# 04_PCIe_VL805.net
KiCad netlist of a schematic drawn in Altium Designer
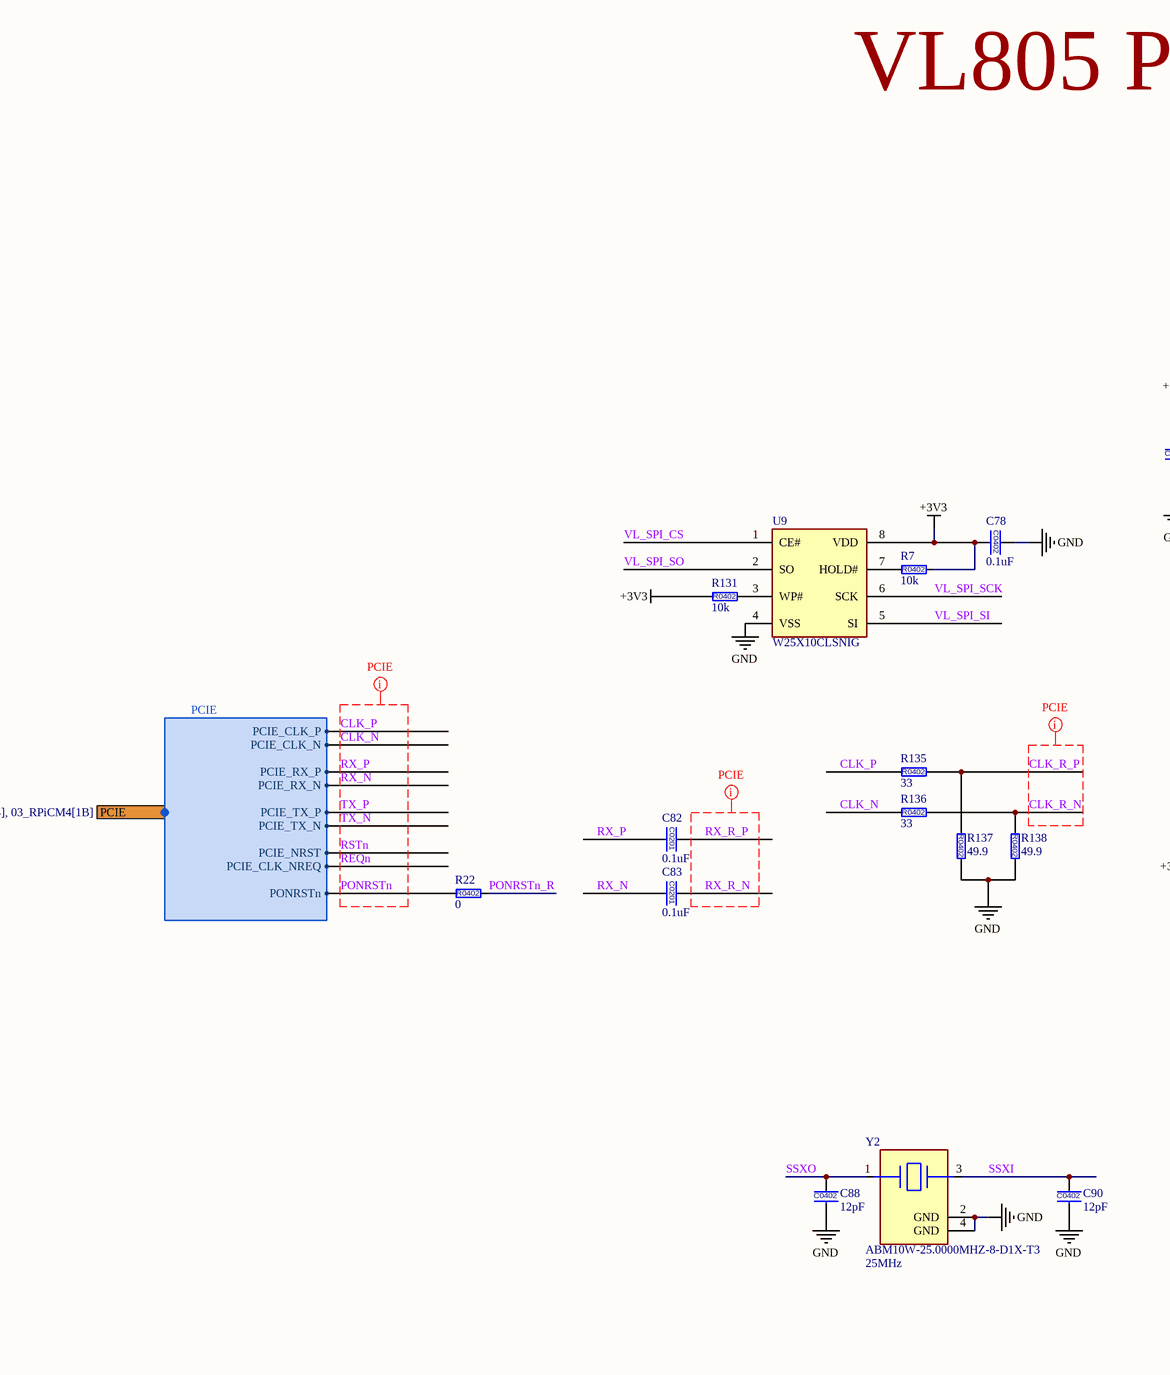
[diagram p0: 04_PCIe_VL805.SchDoc, left]
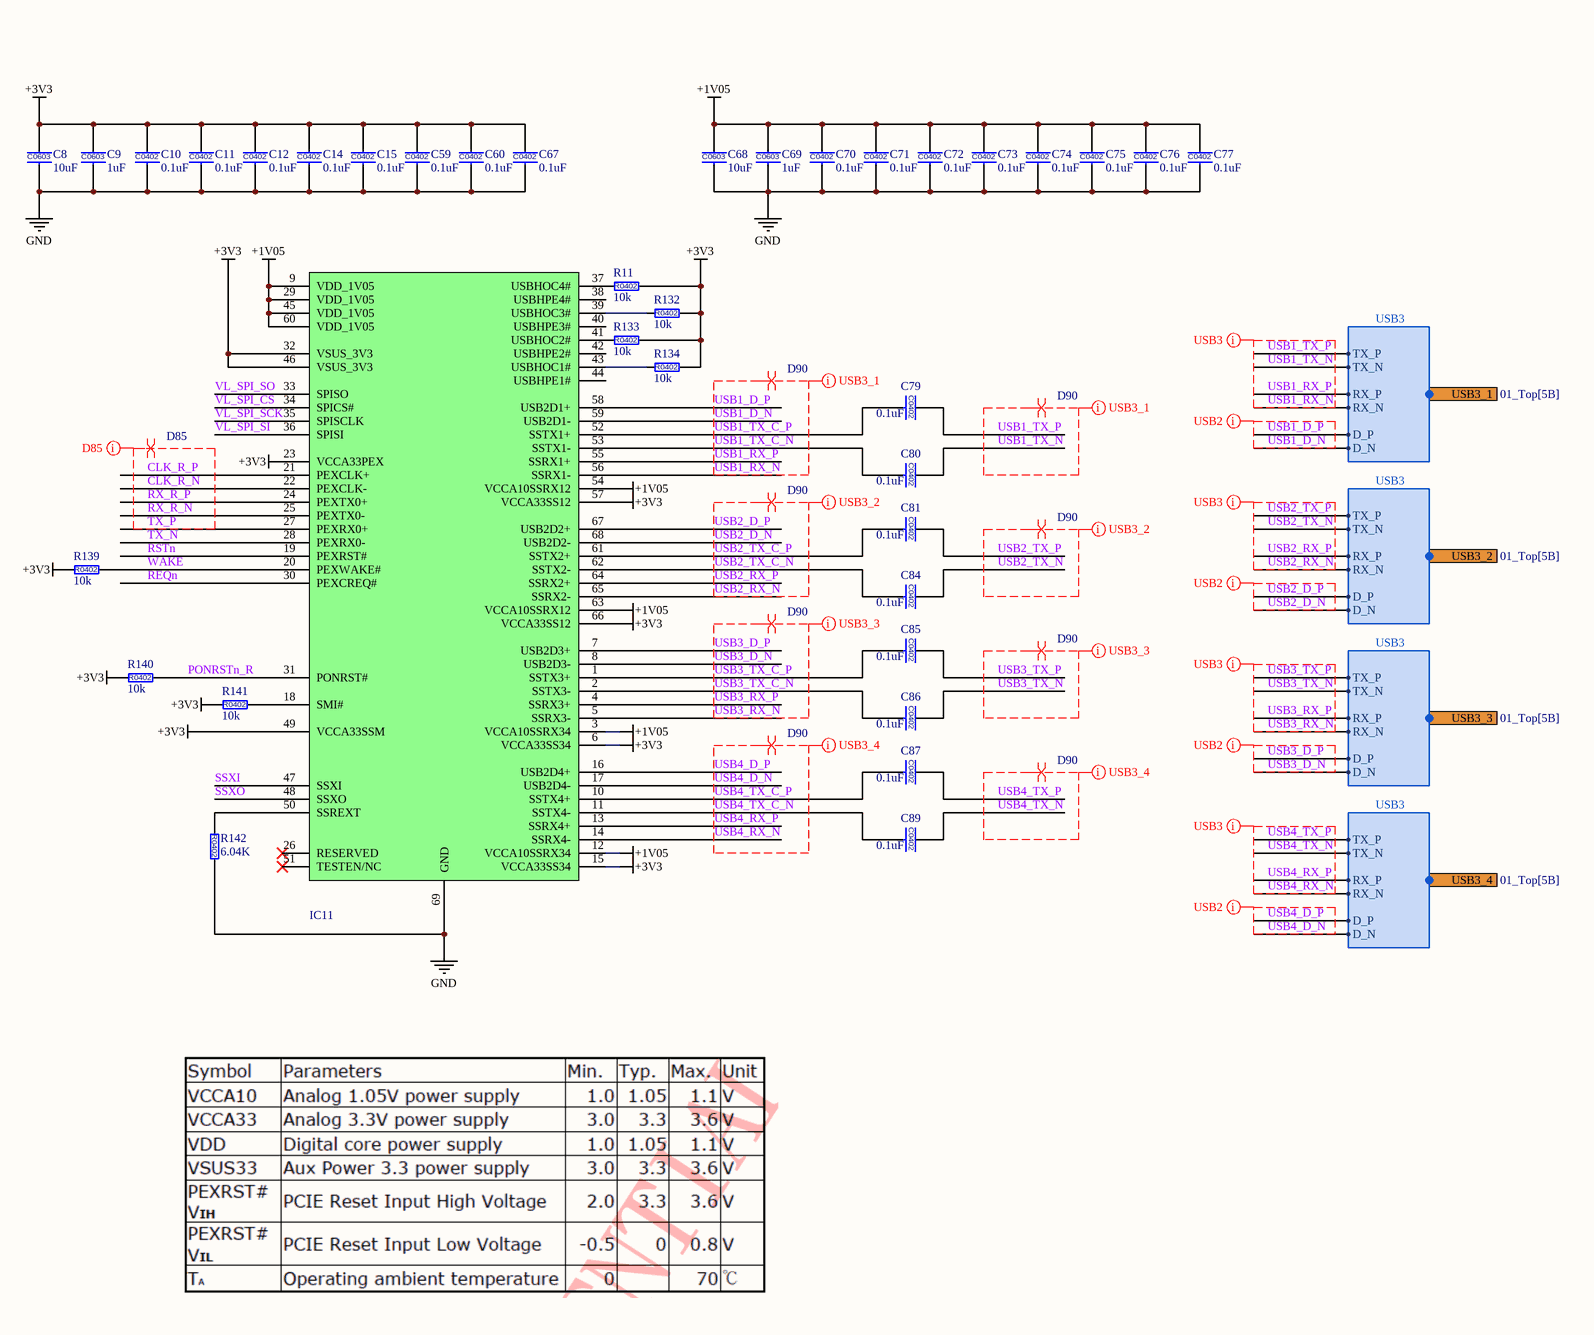
[diagram p1: 04_PCIe_VL805.SchDoc, right]

(export (version "E")
  (design (tool "Eeschema 10.0.6"))
  (components
    (comp (ref "C8")
      (value "10uF")
      (footprint "C0603")
      (description "CAP CER 10uF 10% 10V X5R 0603")
      (fields
        (field (name "MANUFACTURER") "KYOCERA AVX")
        (field (name "MANUFACTURER PART NUMBER") "0603ZD106KAT2A")
      )
      (libsource (lib "Capacitor") (part "0603ZD106KAT2A"))
    )
    (comp (ref "C9")
      (value "1uF")
      (footprint "C0603")
      (description "CAP CER 1uF 20% 10V X5R 0603")
      (fields (field (name "TOLERANCE") "20%") (field (name "MANUFACTURER") "KYOCERA AVX"))
      (libsource (lib "Capacitor") (part "0201ZD105MAT2A"))
    )
    (comp (ref "C10")
      (value "0.1uF")
      (footprint "C0402")
      (description "CAP CER  0.1uF 10% 25V X5R 0402")
      (fields
        (field (name "MANUFACTURER") "AVX Corporation")
        (field (name "MANUFACTURER PART NUMBER") "04023D104KAT2A")
      )
      (libsource (lib "Capacitor") (part "04023D104KAT2A"))
    )
    (comp (ref "C11")
      (value "0.1uF")
      (footprint "C0402")
      (description "CAP CER  0.1uF 10% 25V X5R 0402")
      (fields
        (field (name "MANUFACTURER") "AVX Corporation")
        (field (name "MANUFACTURER PART NUMBER") "04023D104KAT2A")
      )
      (libsource (lib "Capacitor") (part "04023D104KAT2A"))
    )
    (comp (ref "C12")
      (value "0.1uF")
      (footprint "C0402")
      (description "CAP CER  0.1uF 10% 25V X5R 0402")
      (fields
        (field (name "MANUFACTURER") "AVX Corporation")
        (field (name "MANUFACTURER PART NUMBER") "04023D104KAT2A")
      )
      (libsource (lib "Capacitor") (part "04023D104KAT2A"))
    )
    (comp (ref "C14")
      (value "0.1uF")
      (footprint "C0402")
      (description "CAP CER  0.1uF 10% 25V X5R 0402")
      (fields
        (field (name "MANUFACTURER") "AVX Corporation")
        (field (name "MANUFACTURER PART NUMBER") "04023D104KAT2A")
      )
      (libsource (lib "Capacitor") (part "04023D104KAT2A"))
    )
    (comp (ref "C15")
      (value "0.1uF")
      (footprint "C0402")
      (description "CAP CER  0.1uF 10% 25V X5R 0402")
      (fields
        (field (name "MANUFACTURER") "AVX Corporation")
        (field (name "MANUFACTURER PART NUMBER") "04023D104KAT2A")
      )
      (libsource (lib "Capacitor") (part "04023D104KAT2A"))
    )
    (comp (ref "C59")
      (value "0.1uF")
      (footprint "C0402")
      (description "CAP CER  0.1uF 10% 25V X5R 0402")
      (fields
        (field (name "MANUFACTURER") "AVX Corporation")
        (field (name "MANUFACTURER PART NUMBER") "04023D104KAT2A")
      )
      (libsource (lib "Capacitor") (part "04023D104KAT2A"))
    )
    (comp (ref "C60")
      (value "0.1uF")
      (footprint "C0402")
      (description "CAP CER  0.1uF 10% 25V X5R 0402")
      (fields
        (field (name "MANUFACTURER") "AVX Corporation")
        (field (name "MANUFACTURER PART NUMBER") "04023D104KAT2A")
      )
      (libsource (lib "Capacitor") (part "04023D104KAT2A"))
    )
    (comp (ref "C67")
      (value "0.1uF")
      (footprint "C0402")
      (description "CAP CER  0.1uF 10% 25V X5R 0402")
      (fields
        (field (name "MANUFACTURER") "AVX Corporation")
        (field (name "MANUFACTURER PART NUMBER") "04023D104KAT2A")
      )
      (libsource (lib "Capacitor") (part "04023D104KAT2A"))
    )
    (comp (ref "C68")
      (value "10uF")
      (footprint "C0603")
      (description "CAP CER 10uF 10% 10V X5R 0603")
      (fields
        (field (name "MANUFACTURER") "KYOCERA AVX")
        (field (name "MANUFACTURER PART NUMBER") "0603ZD106KAT2A")
      )
      (libsource (lib "Capacitor") (part "0603ZD106KAT2A"))
    )
    (comp (ref "C69")
      (value "1uF")
      (footprint "C0603")
      (description "CAP CER 1uF 20% 10V X5R 0603")
      (fields (field (name "TOLERANCE") "20%") (field (name "MANUFACTURER") "KYOCERA AVX"))
      (libsource (lib "Capacitor") (part "0201ZD105MAT2A"))
    )
    (comp (ref "C70")
      (value "0.1uF")
      (footprint "C0402")
      (description "CAP CER  0.1uF 10% 25V X5R 0402")
      (fields
        (field (name "MANUFACTURER") "AVX Corporation")
        (field (name "MANUFACTURER PART NUMBER") "04023D104KAT2A")
      )
      (libsource (lib "Capacitor") (part "04023D104KAT2A"))
    )
    (comp (ref "C71")
      (value "0.1uF")
      (footprint "C0402")
      (description "CAP CER  0.1uF 10% 25V X5R 0402")
      (fields
        (field (name "MANUFACTURER") "AVX Corporation")
        (field (name "MANUFACTURER PART NUMBER") "04023D104KAT2A")
      )
      (libsource (lib "Capacitor") (part "04023D104KAT2A"))
    )
    (comp (ref "C72")
      (value "0.1uF")
      (footprint "C0402")
      (description "CAP CER  0.1uF 10% 25V X5R 0402")
      (fields
        (field (name "MANUFACTURER") "AVX Corporation")
        (field (name "MANUFACTURER PART NUMBER") "04023D104KAT2A")
      )
      (libsource (lib "Capacitor") (part "04023D104KAT2A"))
    )
    (comp (ref "C73")
      (value "0.1uF")
      (footprint "C0402")
      (description "CAP CER  0.1uF 10% 25V X5R 0402")
      (fields
        (field (name "MANUFACTURER") "AVX Corporation")
        (field (name "MANUFACTURER PART NUMBER") "04023D104KAT2A")
      )
      (libsource (lib "Capacitor") (part "04023D104KAT2A"))
    )
    (comp (ref "C74")
      (value "0.1uF")
      (footprint "C0402")
      (description "CAP CER  0.1uF 10% 25V X5R 0402")
      (fields
        (field (name "MANUFACTURER") "AVX Corporation")
        (field (name "MANUFACTURER PART NUMBER") "04023D104KAT2A")
      )
      (libsource (lib "Capacitor") (part "04023D104KAT2A"))
    )
    (comp (ref "C75")
      (value "0.1uF")
      (footprint "C0402")
      (description "CAP CER  0.1uF 10% 25V X5R 0402")
      (fields
        (field (name "MANUFACTURER") "AVX Corporation")
        (field (name "MANUFACTURER PART NUMBER") "04023D104KAT2A")
      )
      (libsource (lib "Capacitor") (part "04023D104KAT2A"))
    )
    (comp (ref "C76")
      (value "0.1uF")
      (footprint "C0402")
      (description "CAP CER  0.1uF 10% 25V X5R 0402")
      (fields
        (field (name "MANUFACTURER") "AVX Corporation")
        (field (name "MANUFACTURER PART NUMBER") "04023D104KAT2A")
      )
      (libsource (lib "Capacitor") (part "04023D104KAT2A"))
    )
    (comp (ref "C77")
      (value "0.1uF")
      (footprint "C0402")
      (description "CAP CER  0.1uF 10% 25V X5R 0402")
      (fields
        (field (name "MANUFACTURER") "AVX Corporation")
        (field (name "MANUFACTURER PART NUMBER") "04023D104KAT2A")
      )
      (libsource (lib "Capacitor") (part "04023D104KAT2A"))
    )
    (comp (ref "C78")
      (value "0.1uF")
      (footprint "C0402")
      (description "CAP CER  0.1uF 10% 25V X5R 0402")
      (fields
        (field (name "MANUFACTURER") "AVX Corporation")
        (field (name "MANUFACTURER PART NUMBER") "04023D104KAT2A")
      )
      (libsource (lib "Capacitor") (part "04023D104KAT2A"))
    )
    (comp (ref "C79")
      (value "0.1uF")
      (footprint "C0402")
      (description "CAP CER  0.1uF 10% 25V X5R 0402")
      (fields
        (field (name "MANUFACTURER") "AVX Corporation")
        (field (name "MANUFACTURER PART NUMBER") "04023D104KAT2A")
      )
      (libsource (lib "Capacitor") (part "04023D104KAT2A"))
    )
    (comp (ref "C80")
      (value "0.1uF")
      (footprint "C0402")
      (description "CAP CER  0.1uF 10% 25V X5R 0402")
      (fields
        (field (name "MANUFACTURER") "AVX Corporation")
        (field (name "MANUFACTURER PART NUMBER") "04023D104KAT2A")
      )
      (libsource (lib "Capacitor") (part "04023D104KAT2A"))
    )
    (comp (ref "C81")
      (value "0.1uF")
      (footprint "C0402")
      (description "CAP CER  0.1uF 10% 25V X5R 0402")
      (fields
        (field (name "MANUFACTURER") "AVX Corporation")
        (field (name "MANUFACTURER PART NUMBER") "04023D104KAT2A")
      )
      (libsource (lib "Capacitor") (part "04023D104KAT2A"))
    )
    (comp (ref "C82")
      (value "0.1uF")
      (footprint "C0201")
      (description "CAP CER  0.1uF 10% 6.3V X5R 0201")
      (fields
        (field (name "MANUFACTURER") "AVX Corporation")
        (field (name "MANUFACTURER PART NUMBER") "02016D104KAT")
      )
      (libsource (lib "Capacitor") (part "02016D104KAT"))
    )
    (comp (ref "C83")
      (value "0.1uF")
      (footprint "C0201")
      (description "CAP CER  0.1uF 10% 6.3V X5R 0201")
      (fields
        (field (name "MANUFACTURER") "AVX Corporation")
        (field (name "MANUFACTURER PART NUMBER") "02016D104KAT")
      )
      (libsource (lib "Capacitor") (part "02016D104KAT"))
    )
    (comp (ref "C84")
      (value "0.1uF")
      (footprint "C0402")
      (description "CAP CER  0.1uF 10% 25V X5R 0402")
      (fields
        (field (name "MANUFACTURER") "AVX Corporation")
        (field (name "MANUFACTURER PART NUMBER") "04023D104KAT2A")
      )
      (libsource (lib "Capacitor") (part "04023D104KAT2A"))
    )
    (comp (ref "C85")
      (value "0.1uF")
      (footprint "C0402")
      (description "CAP CER  0.1uF 10% 25V X5R 0402")
      (fields
        (field (name "MANUFACTURER") "AVX Corporation")
        (field (name "MANUFACTURER PART NUMBER") "04023D104KAT2A")
      )
      (libsource (lib "Capacitor") (part "04023D104KAT2A"))
    )
    (comp (ref "C86")
      (value "0.1uF")
      (footprint "C0402")
      (description "CAP CER  0.1uF 10% 25V X5R 0402")
      (fields
        (field (name "MANUFACTURER") "AVX Corporation")
        (field (name "MANUFACTURER PART NUMBER") "04023D104KAT2A")
      )
      (libsource (lib "Capacitor") (part "04023D104KAT2A"))
    )
    (comp (ref "C87")
      (value "0.1uF")
      (footprint "C0402")
      (description "CAP CER  0.1uF 10% 25V X5R 0402")
      (fields
        (field (name "MANUFACTURER") "AVX Corporation")
        (field (name "MANUFACTURER PART NUMBER") "04023D104KAT2A")
      )
      (libsource (lib "Capacitor") (part "04023D104KAT2A"))
    )
    (comp (ref "C88")
      (value "12pF")
      (footprint "C0402")
      (description "CAP CER 12pF 10% 25V NP0 0402")
      (fields
        (field (name "MANUFACTURER") "KYOCERA AVX")
        (field (name "MANUFACTURER PART NUMBER") "04023A120KAT2A")
      )
      (libsource (lib "Capacitor") (part "04023A120KAT2A"))
    )
    (comp (ref "C89")
      (value "0.1uF")
      (footprint "C0402")
      (description "CAP CER  0.1uF 10% 25V X5R 0402")
      (fields
        (field (name "MANUFACTURER") "AVX Corporation")
        (field (name "MANUFACTURER PART NUMBER") "04023D104KAT2A")
      )
      (libsource (lib "Capacitor") (part "04023D104KAT2A"))
    )
    (comp (ref "C90")
      (value "12pF")
      (footprint "C0402")
      (description "CAP CER 12pF 10% 25V NP0 0402")
      (fields
        (field (name "MANUFACTURER") "KYOCERA AVX")
        (field (name "MANUFACTURER PART NUMBER") "04023A120KAT2A")
      )
      (libsource (lib "Capacitor") (part "04023A120KAT2A"))
    )
    (comp (ref "IC11")
      (value "VL805-Q6")
      (footprint "VL805-Q6_QFN-68G")
      (description "VL805 4-Port USB 3.0 Host Controller")
      (fields (field (name "MANUFACTURER") "VLI"))
      (libsource (lib "new") (part "VL805-Q6"))
    )
    (comp (ref "R7")
      (value "10k")
      (footprint "R0402")
      (description "RES SMD 10K ohm 1% 1/16W R0402")
      (fields
        (field (name "MANUFACTURER") "Vishay Dale")
        (field (name "MANUFACTURER PART NUMBER") "CRCW040210K0FK")
      )
      (libsource (lib "Resistor") (part "CRCW040210K0FK"))
    )
    (comp (ref "R11")
      (value "10k")
      (footprint "R0402")
      (description "RES SMD 10K ohm 1% 1/16W R0402")
      (fields
        (field (name "MANUFACTURER") "Vishay")
        (field (name "MANUFACTURER PART NUMBER") "CRCW040210K0FK")
      )
      (libsource (lib "Resistor") (part "CRCW040210K0FK"))
    )
    (comp (ref "R22")
      (value "0")
      (footprint "R0402")
      (description "RES SMD 0 ohm 1/16W R0402")
      (fields
        (field (name "MANUFACTURER") "Vishay Dale")
        (field (name "MANUFACTURER PART NUMBER") "CRCW04020000Z0")
      )
      (libsource (lib "Resistor") (part "CRCW04020000Z0"))
    )
    (comp (ref "R131")
      (value "10k")
      (footprint "R0402")
      (description "RES SMD 10K ohm 1% 1/16W R0402")
      (fields
        (field (name "MANUFACTURER") "Vishay Dale")
        (field (name "MANUFACTURER PART NUMBER") "CRCW040210K0FK")
      )
      (libsource (lib "Resistor") (part "CRCW040210K0FK"))
    )
    (comp (ref "R132")
      (value "10k")
      (footprint "R0402")
      (description "RES SMD 10K ohm 1% 1/16W R0402")
      (fields
        (field (name "MANUFACTURER") "Vishay")
        (field (name "MANUFACTURER PART NUMBER") "CRCW040210K0FK")
      )
      (libsource (lib "Resistor") (part "CRCW040210K0FK"))
    )
    (comp (ref "R133")
      (value "10k")
      (footprint "R0402")
      (description "RES SMD 10K ohm 1% 1/16W R0402")
      (fields
        (field (name "MANUFACTURER") "Vishay")
        (field (name "MANUFACTURER PART NUMBER") "CRCW040210K0FK")
      )
      (libsource (lib "Resistor") (part "CRCW040210K0FK"))
    )
    (comp (ref "R134")
      (value "10k")
      (footprint "R0402")
      (description "RES SMD 10K ohm 1% 1/16W R0402")
      (fields
        (field (name "MANUFACTURER") "Vishay")
        (field (name "MANUFACTURER PART NUMBER") "CRCW040210K0FK")
      )
      (libsource (lib "Resistor") (part "CRCW040210K0FK"))
    )
    (comp (ref "R135")
      (value "33")
      (footprint "R0402")
      (description "RES SMD 33 ohm 1% 1/16W R0402")
      (fields
        (field (name "MANUFACTURER") "Vishay")
        (field (name "MANUFACTURER PART NUMBER") "CRCW040233R0FKEDC")
      )
      (libsource (lib "Resistor") (part "CRCW040233R0FKEDC"))
    )
    (comp (ref "R136")
      (value "33")
      (footprint "R0402")
      (description "RES SMD 33 ohm 1% 1/16W R0402")
      (fields
        (field (name "MANUFACTURER") "Vishay")
        (field (name "MANUFACTURER PART NUMBER") "CRCW040233R0FKEDC")
      )
      (libsource (lib "Resistor") (part "CRCW040233R0FKEDC"))
    )
    (comp (ref "R137")
      (value "49.9")
      (footprint "R0402")
      (description "RES SMD 49.9 ohm 1% 1/16W R0402")
      (fields
        (field (name "MANUFACTURER") "Vishay")
        (field (name "MANUFACTURER PART NUMBER") "CRCW040249R9FKEDC")
      )
      (libsource (lib "Resistor") (part "CRCW040249R9FKEDC"))
    )
    (comp (ref "R138")
      (value "49.9")
      (footprint "R0402")
      (description "RES SMD 49.9 ohm 1% 1/16W R0402")
      (fields
        (field (name "MANUFACTURER") "Vishay")
        (field (name "MANUFACTURER PART NUMBER") "CRCW040249R9FKEDC")
      )
      (libsource (lib "Resistor") (part "CRCW040249R9FKEDC"))
    )
    (comp (ref "R139")
      (value "10k")
      (footprint "R0402")
      (description "RES SMD 10K ohm 1% 1/16W R0402")
      (fields
        (field (name "MANUFACTURER") "Vishay")
        (field (name "MANUFACTURER PART NUMBER") "CRCW040210K0FK")
      )
      (libsource (lib "Resistor") (part "CRCW040210K0FK"))
    )
    (comp (ref "R140")
      (value "10k")
      (footprint "R0402")
      (description "RES SMD 10K ohm 1% 1/16W R0402")
      (fields
        (field (name "MANUFACTURER") "Vishay")
        (field (name "MANUFACTURER PART NUMBER") "CRCW040210K0FK")
      )
      (libsource (lib "Resistor") (part "CRCW040210K0FK"))
    )
    (comp (ref "R141")
      (value "10k")
      (footprint "R0402")
      (description "RES SMD 10K ohm 1% 1/16W R0402")
      (fields
        (field (name "MANUFACTURER") "Vishay")
        (field (name "MANUFACTURER PART NUMBER") "CRCW040210K0FK")
      )
      (libsource (lib "Resistor") (part "CRCW040210K0FK"))
    )
    (comp (ref "R142")
      (value "6.04K")
      (footprint "R0402")
      (description "RES SMD6.04K ohm 1% 1/16W R0402")
      (fields
        (field (name "MANUFACTURER") "Vishay")
        (field (name "MANUFACTURER PART NUMBER") "CRCW04026K04FKEDC")
      )
      (libsource (lib "Resistor") (part "CRCW04026K04FKEDC"))
    )
    (comp (ref "U9")
      (value "W25X10CLSNIG")
      (footprint "W25X10CLSNIG_SOIC_8")
      (description "IC FLASH 1MBIT 104MHZ 8SOIC")
      (fields (field (name "MANUFACTURER") "Winbond"))
      (libsource (lib "new") (part "W25X10CLSNIG"))
    )
    (comp (ref "Y2")
      (value "ABM10W-25.0000MHZ-8-D1X-T3")
      (footprint "ABM10W")
      (description "CRYSTAL 25.0000MHZ 8PF SMD, 2.5x2mm, RoHS")
      (fields (field (name "MANUFACTURER") "Abracon") (field (name "FREQUENCY") "25MHz"))
      (libsource (lib "new") (part "ABM10W-25.0000MHZ-8-D1X-T3"))
    )
  )
  (nets
    (net (code "3") (name "+1V05") (class "Default")
      (node (ref "C68") (pin "1") (pinfunction "1_1") (pintype "passive"))
      (node (ref "C69") (pin "1") (pinfunction "1_1") (pintype "passive"))
      (node (ref "C70") (pin "1") (pinfunction "1_1") (pintype "passive"))
      (node (ref "C71") (pin "1") (pinfunction "1_1") (pintype "passive"))
      (node (ref "C72") (pin "1") (pinfunction "1_1") (pintype "passive"))
      (node (ref "C73") (pin "1") (pinfunction "1_1") (pintype "passive"))
      (node (ref "C74") (pin "1") (pinfunction "1_1") (pintype "passive"))
      (node (ref "C75") (pin "1") (pinfunction "1_1") (pintype "passive"))
      (node (ref "C76") (pin "1") (pinfunction "1_1") (pintype "passive"))
      (node (ref "C77") (pin "1") (pinfunction "1_1") (pintype "passive"))
      (node (ref "IC11") (pin "12") (pinfunction "VCCA10SSRX34_12") (pintype "passive"))
      (node (ref "IC11") (pin "29") (pinfunction "VDD_1V05_29") (pintype "passive"))
      (node (ref "IC11") (pin "3") (pinfunction "VCCA10SSRX34_3") (pintype "passive"))
      (node (ref "IC11") (pin "45") (pinfunction "VDD_1V05_45") (pintype "passive"))
      (node (ref "IC11") (pin "54") (pinfunction "VCCA10SSRX12_54") (pintype "passive"))
      (node (ref "IC11") (pin "60") (pinfunction "VDD_1V05_60") (pintype "passive"))
      (node (ref "IC11") (pin "63") (pinfunction "VCCA10SSRX12_63") (pintype "passive"))
      (node (ref "IC11") (pin "9") (pinfunction "VDD_1V05_9") (pintype "passive"))
    )
    (net (code "4") (name "+3V3") (class "Default")
      (node (ref "C10") (pin "1") (pinfunction "1_1") (pintype "passive"))
      (node (ref "C11") (pin "1") (pinfunction "1_1") (pintype "passive"))
      (node (ref "C12") (pin "1") (pinfunction "1_1") (pintype "passive"))
      (node (ref "C14") (pin "1") (pinfunction "1_1") (pintype "passive"))
      (node (ref "C15") (pin "1") (pinfunction "1_1") (pintype "passive"))
      (node (ref "C59") (pin "1") (pinfunction "1_1") (pintype "passive"))
      (node (ref "C60") (pin "1") (pinfunction "1_1") (pintype "passive"))
      (node (ref "C67") (pin "1") (pinfunction "1_1") (pintype "passive"))
      (node (ref "C78") (pin "2") (pinfunction "2_2") (pintype "passive"))
      (node (ref "C8") (pin "1") (pinfunction "1_1") (pintype "passive"))
      (node (ref "C9") (pin "1") (pinfunction "1_1") (pintype "passive"))
      (node (ref "IC11") (pin "15") (pinfunction "VCCA33SS34_15") (pintype "passive"))
      (node (ref "IC11") (pin "23") (pinfunction "VCCA33PEX_23") (pintype "passive"))
      (node (ref "IC11") (pin "32") (pinfunction "VSUS_3V3_32") (pintype "passive"))
      (node (ref "IC11") (pin "46") (pinfunction "VSUS_3V3_46") (pintype "passive"))
      (node (ref "IC11") (pin "49") (pinfunction "VCCA33SSM_49") (pintype "passive"))
      (node (ref "IC11") (pin "57") (pinfunction "VCCA33SS12_57") (pintype "passive"))
      (node (ref "IC11") (pin "6") (pinfunction "VCCA33SS34_6") (pintype "passive"))
      (node (ref "IC11") (pin "66") (pinfunction "VCCA33SS12_66") (pintype "passive"))
      (node (ref "R11") (pin "2") (pinfunction "2_2") (pintype "passive"))
      (node (ref "R131") (pin "1") (pinfunction "1_1") (pintype "passive"))
      (node (ref "R132") (pin "2") (pinfunction "2_2") (pintype "passive"))
      (node (ref "R133") (pin "2") (pinfunction "2_2") (pintype "passive"))
      (node (ref "R134") (pin "2") (pinfunction "2_2") (pintype "passive"))
      (node (ref "R139") (pin "1") (pinfunction "1_1") (pintype "passive"))
      (node (ref "R140") (pin "1") (pinfunction "1_1") (pintype "passive"))
      (node (ref "R141") (pin "1") (pinfunction "1_1") (pintype "passive"))
      (node (ref "R7") (pin "2") (pinfunction "2_2") (pintype "passive"))
      (node (ref "U9") (pin "8") (pinfunction "VDD_8") (pintype "passive"))
    )
    (net (code "5") (name "/CLK_N") (class "Default")
      (node (ref "R136") (pin "1") (pinfunction "1_1") (pintype "passive"))
    )
    (net (code "6") (name "/CLK_P") (class "Default")
      (node (ref "R135") (pin "1") (pinfunction "1_1") (pintype "passive"))
    )
    (net (code "7") (name "/CLK_R_N") (class "Default")
      (node (ref "IC11") (pin "22") (pinfunction "PEXCLK-_22") (pintype "passive"))
      (node (ref "R136") (pin "2") (pinfunction "2_2") (pintype "passive"))
      (node (ref "R138") (pin "1") (pinfunction "1_1") (pintype "passive"))
    )
    (net (code "8") (name "/CLK_R_P") (class "Default")
      (node (ref "IC11") (pin "21") (pinfunction "PEXCLK+_21") (pintype "passive"))
      (node (ref "R135") (pin "2") (pinfunction "2_2") (pintype "passive"))
      (node (ref "R137") (pin "1") (pinfunction "1_1") (pintype "passive"))
    )
    (net (code "9") (name "/PONRSTn") (class "Default")
      (node (ref "R22") (pin "1") (pinfunction "1_1") (pintype "passive"))
    )
    (net (code "10") (name "/PONRSTn_R") (class "Default")
      (node (ref "IC11") (pin "31") (pinfunction "PONRST#_31") (pintype "passive"))
      (node (ref "R140") (pin "2") (pinfunction "2_2") (pintype "passive"))
      (node (ref "R22") (pin "2") (pinfunction "2_2") (pintype "passive"))
    )
    (net (code "11") (name "/REQn") (class "Default")
      (node (ref "IC11") (pin "30") (pinfunction "PEXCREQ#_30") (pintype "passive"))
    )
    (net (code "12") (name "/RSTn") (class "Default")
      (node (ref "IC11") (pin "19") (pinfunction "PEXRST#_19") (pintype "passive"))
    )
    (net (code "13") (name "/RX_N") (class "Default")
      (node (ref "C83") (pin "2") (pinfunction "2_2") (pintype "passive"))
    )
    (net (code "14") (name "/RX_P") (class "Default")
      (node (ref "C82") (pin "2") (pinfunction "2_2") (pintype "passive"))
    )
    (net (code "15") (name "/RX_R_N") (class "Default")
      (node (ref "C83") (pin "1") (pinfunction "1_1") (pintype "passive"))
      (node (ref "IC11") (pin "25") (pinfunction "PEXTX0-_25") (pintype "passive"))
    )
    (net (code "16") (name "/RX_R_P") (class "Default")
      (node (ref "C82") (pin "1") (pinfunction "1_1") (pintype "passive"))
      (node (ref "IC11") (pin "24") (pinfunction "PEXTX0+_24") (pintype "passive"))
    )
    (net (code "17") (name "/SSXI") (class "Default")
      (node (ref "C90") (pin "1") (pinfunction "1_1") (pintype "passive"))
      (node (ref "IC11") (pin "47") (pinfunction "SSXI_47") (pintype "passive"))
      (node (ref "Y2") (pin "3") (pinfunction "3_3") (pintype "passive"))
    )
    (net (code "18") (name "/SSXO") (class "Default")
      (node (ref "C88") (pin "1") (pinfunction "1_1") (pintype "passive"))
      (node (ref "IC11") (pin "48") (pinfunction "SSXO_48") (pintype "passive"))
      (node (ref "Y2") (pin "1") (pinfunction "1_1") (pintype "passive"))
    )
    (net (code "19") (name "/TX_N") (class "Default")
      (node (ref "IC11") (pin "28") (pinfunction "PEXRX0-_28") (pintype "passive"))
    )
    (net (code "20") (name "/TX_P") (class "Default")
      (node (ref "IC11") (pin "27") (pinfunction "PEXRX0+_27") (pintype "passive"))
    )
    (net (code "21") (name "/USB1_D_N") (class "Default")
      (node (ref "IC11") (pin "59") (pinfunction "USB2D1-_59") (pintype "passive"))
    )
    (net (code "22") (name "/USB1_D_P") (class "Default")
      (node (ref "IC11") (pin "58") (pinfunction "USB2D1+_58") (pintype "passive"))
    )
    (net (code "23") (name "/USB1_RX_N") (class "Default")
      (node (ref "IC11") (pin "56") (pinfunction "SSRX1-_56") (pintype "passive"))
    )
    (net (code "24") (name "/USB1_RX_P") (class "Default")
      (node (ref "IC11") (pin "55") (pinfunction "SSRX1+_55") (pintype "passive"))
    )
    (net (code "25") (name "/USB1_TX_C_N") (class "Default")
      (node (ref "C80") (pin "2") (pinfunction "2_2") (pintype "passive"))
      (node (ref "IC11") (pin "53") (pinfunction "SSTX1-_53") (pintype "passive"))
    )
    (net (code "26") (name "/USB1_TX_C_P") (class "Default")
      (node (ref "C79") (pin "2") (pinfunction "2_2") (pintype "passive"))
      (node (ref "IC11") (pin "52") (pinfunction "SSTX1+_52") (pintype "passive"))
    )
    (net (code "27") (name "/USB1_TX_N") (class "Default")
      (node (ref "C80") (pin "1") (pinfunction "1_1") (pintype "passive"))
    )
    (net (code "28") (name "/USB1_TX_P") (class "Default")
      (node (ref "C79") (pin "1") (pinfunction "1_1") (pintype "passive"))
    )
    (net (code "29") (name "/USB2_D_N") (class "Default")
      (node (ref "IC11") (pin "68") (pinfunction "USB2D2-_68") (pintype "passive"))
    )
    (net (code "30") (name "/USB2_D_P") (class "Default")
      (node (ref "IC11") (pin "67") (pinfunction "USB2D2+_67") (pintype "passive"))
    )
    (net (code "31") (name "/USB2_RX_N") (class "Default")
      (node (ref "IC11") (pin "65") (pinfunction "SSRX2-_65") (pintype "passive"))
    )
    (net (code "32") (name "/USB2_RX_P") (class "Default")
      (node (ref "IC11") (pin "64") (pinfunction "SSRX2+_64") (pintype "passive"))
    )
    (net (code "33") (name "/USB2_TX_C_N") (class "Default")
      (node (ref "C84") (pin "2") (pinfunction "2_2") (pintype "passive"))
      (node (ref "IC11") (pin "62") (pinfunction "SSTX2-_62") (pintype "passive"))
    )
    (net (code "34") (name "/USB2_TX_C_P") (class "Default")
      (node (ref "C81") (pin "2") (pinfunction "2_2") (pintype "passive"))
      (node (ref "IC11") (pin "61") (pinfunction "SSTX2+_61") (pintype "passive"))
    )
    (net (code "35") (name "/USB2_TX_N") (class "Default")
      (node (ref "C84") (pin "1") (pinfunction "1_1") (pintype "passive"))
    )
    (net (code "36") (name "/USB2_TX_P") (class "Default")
      (node (ref "C81") (pin "1") (pinfunction "1_1") (pintype "passive"))
    )
    (net (code "37") (name "/USB3_D_N") (class "Default")
      (node (ref "IC11") (pin "8") (pinfunction "USB2D3-_8") (pintype "passive"))
    )
    (net (code "38") (name "/USB3_D_P") (class "Default")
      (node (ref "IC11") (pin "7") (pinfunction "USB2D3+_7") (pintype "passive"))
    )
    (net (code "39") (name "/USB3_RX_N") (class "Default")
      (node (ref "IC11") (pin "5") (pinfunction "SSRX3-_5") (pintype "passive"))
    )
    (net (code "40") (name "/USB3_RX_P") (class "Default")
      (node (ref "IC11") (pin "4") (pinfunction "SSRX3+_4") (pintype "passive"))
    )
    (net (code "41") (name "/USB3_TX_C_N") (class "Default")
      (node (ref "C86") (pin "2") (pinfunction "2_2") (pintype "passive"))
      (node (ref "IC11") (pin "2") (pinfunction "SSTX3-_2") (pintype "passive"))
    )
    (net (code "42") (name "/USB3_TX_C_P") (class "Default")
      (node (ref "C85") (pin "2") (pinfunction "2_2") (pintype "passive"))
      (node (ref "IC11") (pin "1") (pinfunction "SSTX3+_1") (pintype "passive"))
    )
    (net (code "43") (name "/USB3_TX_N") (class "Default")
      (node (ref "C86") (pin "1") (pinfunction "1_1") (pintype "passive"))
    )
    (net (code "44") (name "/USB3_TX_P") (class "Default")
      (node (ref "C85") (pin "1") (pinfunction "1_1") (pintype "passive"))
    )
    (net (code "45") (name "/USB4_D_N") (class "Default")
      (node (ref "IC11") (pin "17") (pinfunction "USB2D4-_17") (pintype "passive"))
    )
    (net (code "46") (name "/USB4_D_P") (class "Default")
      (node (ref "IC11") (pin "16") (pinfunction "USB2D4+_16") (pintype "passive"))
    )
    (net (code "47") (name "/USB4_RX_N") (class "Default")
      (node (ref "IC11") (pin "14") (pinfunction "SSRX4-_14") (pintype "passive"))
    )
    (net (code "48") (name "/USB4_RX_P") (class "Default")
      (node (ref "IC11") (pin "13") (pinfunction "SSRX4+_13") (pintype "passive"))
    )
    (net (code "49") (name "/USB4_TX_C_N") (class "Default")
      (node (ref "C89") (pin "2") (pinfunction "2_2") (pintype "passive"))
      (node (ref "IC11") (pin "11") (pinfunction "SSTX4-_11") (pintype "passive"))
    )
    (net (code "50") (name "/USB4_TX_C_P") (class "Default")
      (node (ref "C87") (pin "2") (pinfunction "2_2") (pintype "passive"))
      (node (ref "IC11") (pin "10") (pinfunction "SSTX4+_10") (pintype "passive"))
    )
    (net (code "51") (name "/USB4_TX_N") (class "Default")
      (node (ref "C89") (pin "1") (pinfunction "1_1") (pintype "passive"))
    )
    (net (code "52") (name "/USB4_TX_P") (class "Default")
      (node (ref "C87") (pin "1") (pinfunction "1_1") (pintype "passive"))
    )
    (net (code "53") (name "/VL_SPI_CS") (class "Default")
      (node (ref "IC11") (pin "34") (pinfunction "SPICS#_34") (pintype "passive"))
      (node (ref "U9") (pin "1") (pinfunction "CE#_1") (pintype "passive"))
    )
    (net (code "54") (name "/VL_SPI_SCK") (class "Default")
      (node (ref "IC11") (pin "35") (pinfunction "SPISCLK_35") (pintype "passive"))
      (node (ref "U9") (pin "6") (pinfunction "SCK_6") (pintype "passive"))
    )
    (net (code "55") (name "/VL_SPI_SI") (class "Default")
      (node (ref "IC11") (pin "36") (pinfunction "SPISI_36") (pintype "passive"))
      (node (ref "U9") (pin "5") (pinfunction "SI_5") (pintype "passive"))
    )
    (net (code "56") (name "/VL_SPI_SO") (class "Default")
      (node (ref "IC11") (pin "33") (pinfunction "SPISO_33") (pintype "passive"))
      (node (ref "U9") (pin "2") (pinfunction "SO_2") (pintype "passive"))
    )
    (net (code "57") (name "/WAKE") (class "Default")
      (node (ref "IC11") (pin "20") (pinfunction "PEXWAKE#_20") (pintype "passive"))
      (node (ref "R139") (pin "2") (pinfunction "2_2") (pintype "passive"))
    )
    (net (code "60") (name "GND") (class "Default")
      (node (ref "C10") (pin "2") (pinfunction "2_2") (pintype "passive"))
      (node (ref "C11") (pin "2") (pinfunction "2_2") (pintype "passive"))
      (node (ref "C12") (pin "2") (pinfunction "2_2") (pintype "passive"))
      (node (ref "C14") (pin "2") (pinfunction "2_2") (pintype "passive"))
      (node (ref "C15") (pin "2") (pinfunction "2_2") (pintype "passive"))
      (node (ref "C59") (pin "2") (pinfunction "2_2") (pintype "passive"))
      (node (ref "C60") (pin "2") (pinfunction "2_2") (pintype "passive"))
      (node (ref "C67") (pin "2") (pinfunction "2_2") (pintype "passive"))
      (node (ref "C68") (pin "2") (pinfunction "2_2") (pintype "passive"))
      (node (ref "C69") (pin "2") (pinfunction "2_2") (pintype "passive"))
      (node (ref "C70") (pin "2") (pinfunction "2_2") (pintype "passive"))
      (node (ref "C71") (pin "2") (pinfunction "2_2") (pintype "passive"))
      (node (ref "C72") (pin "2") (pinfunction "2_2") (pintype "passive"))
      (node (ref "C73") (pin "2") (pinfunction "2_2") (pintype "passive"))
      (node (ref "C74") (pin "2") (pinfunction "2_2") (pintype "passive"))
      (node (ref "C75") (pin "2") (pinfunction "2_2") (pintype "passive"))
      (node (ref "C76") (pin "2") (pinfunction "2_2") (pintype "passive"))
      (node (ref "C77") (pin "2") (pinfunction "2_2") (pintype "passive"))
      (node (ref "C78") (pin "1") (pinfunction "1_1") (pintype "passive"))
      (node (ref "C8") (pin "2") (pinfunction "2_2") (pintype "passive"))
      (node (ref "C88") (pin "2") (pinfunction "2_2") (pintype "passive"))
      (node (ref "C9") (pin "2") (pinfunction "2_2") (pintype "passive"))
      (node (ref "C90") (pin "2") (pinfunction "2_2") (pintype "passive"))
      (node (ref "IC11") (pin "69") (pinfunction "GND_69") (pintype "passive"))
      (node (ref "R137") (pin "2") (pinfunction "2_2") (pintype "passive"))
      (node (ref "R138") (pin "2") (pinfunction "2_2") (pintype "passive"))
      (node (ref "R142") (pin "2") (pinfunction "2_2") (pintype "passive"))
      (node (ref "U9") (pin "4") (pinfunction "VSS_4") (pintype "passive"))
      (node (ref "Y2") (pin "2") (pinfunction "GND_2") (pintype "power_in"))
      (node (ref "Y2") (pin "4") (pinfunction "GND_4") (pintype "power_in"))
    )
    (net (code "61") (name "Net-(IC11-SMI#)") (class "Default")
      (node (ref "IC11") (pin "18") (pinfunction "SMI#_18") (pintype "passive"))
      (node (ref "R141") (pin "2") (pinfunction "2_2") (pintype "passive"))
    )
    (net (code "62") (name "Net-(IC11-SSREXT)") (class "Default")
      (node (ref "IC11") (pin "50") (pinfunction "SSREXT_50") (pintype "passive"))
      (node (ref "R142") (pin "1") (pinfunction "1_1") (pintype "passive"))
    )
    (net (code "63") (name "Net-(IC11-USBHOC1#)") (class "Default")
      (node (ref "IC11") (pin "43") (pinfunction "USBHOC1#_43") (pintype "passive"))
      (node (ref "R134") (pin "1") (pinfunction "1_1") (pintype "passive"))
    )
    (net (code "64") (name "Net-(IC11-USBHOC2#)") (class "Default")
      (node (ref "IC11") (pin "41") (pinfunction "USBHOC2#_41") (pintype "passive"))
      (node (ref "R133") (pin "1") (pinfunction "1_1") (pintype "passive"))
    )
    (net (code "65") (name "Net-(IC11-USBHOC3#)") (class "Default")
      (node (ref "IC11") (pin "39") (pinfunction "USBHOC3#_39") (pintype "passive"))
      (node (ref "R132") (pin "1") (pinfunction "1_1") (pintype "passive"))
    )
    (net (code "66") (name "Net-(IC11-USBHOC4#)") (class "Default")
      (node (ref "IC11") (pin "37") (pinfunction "USBHOC4#_37") (pintype "passive"))
      (node (ref "R11") (pin "1") (pinfunction "1_1") (pintype "passive"))
    )
    (net (code "67") (name "Net-(U9-HOLD#)") (class "Default")
      (node (ref "R7") (pin "1") (pinfunction "1_1") (pintype "passive"))
      (node (ref "U9") (pin "7") (pinfunction "HOLD#_7") (pintype "passive"))
    )
    (net (code "68") (name "Net-(U9-WP#)") (class "Default")
      (node (ref "R131") (pin "2") (pinfunction "2_2") (pintype "passive"))
      (node (ref "U9") (pin "3") (pinfunction "WP#_3") (pintype "passive"))
    )
    (net (code "69") (name "unconnected-(IC11-RESERVED-Pad26)") (class "Default")
      (node (ref "IC11") (pin "26") (pinfunction "RESERVED_26") (pintype "passive+no_connect"))
    )
    (net (code "70") (name "unconnected-(IC11-TESTEN{slash}NC-Pad51)") (class "Default")
      (node (ref "IC11") (pin "51") (pinfunction "TESTEN/NC_51") (pintype "passive+no_connect"))
    )
    (net (code "71") (name "unconnected-(IC11-USBHPE1#-Pad44)") (class "Default")
      (node (ref "IC11") (pin "44") (pinfunction "USBHPE1#_44") (pintype "passive"))
    )
    (net (code "72") (name "unconnected-(IC11-USBHPE2#-Pad42)") (class "Default")
      (node (ref "IC11") (pin "42") (pinfunction "USBHPE2#_42") (pintype "passive"))
    )
    (net (code "73") (name "unconnected-(IC11-USBHPE3#-Pad40)") (class "Default")
      (node (ref "IC11") (pin "40") (pinfunction "USBHPE3#_40") (pintype "passive"))
    )
    (net (code "74") (name "unconnected-(IC11-USBHPE4#-Pad38)") (class "Default")
      (node (ref "IC11") (pin "38") (pinfunction "USBHPE4#_38") (pintype "passive"))
    )
  )
)
